# regBlock_slice.net
KiCad netlist of a schematic drawn in EAGLE
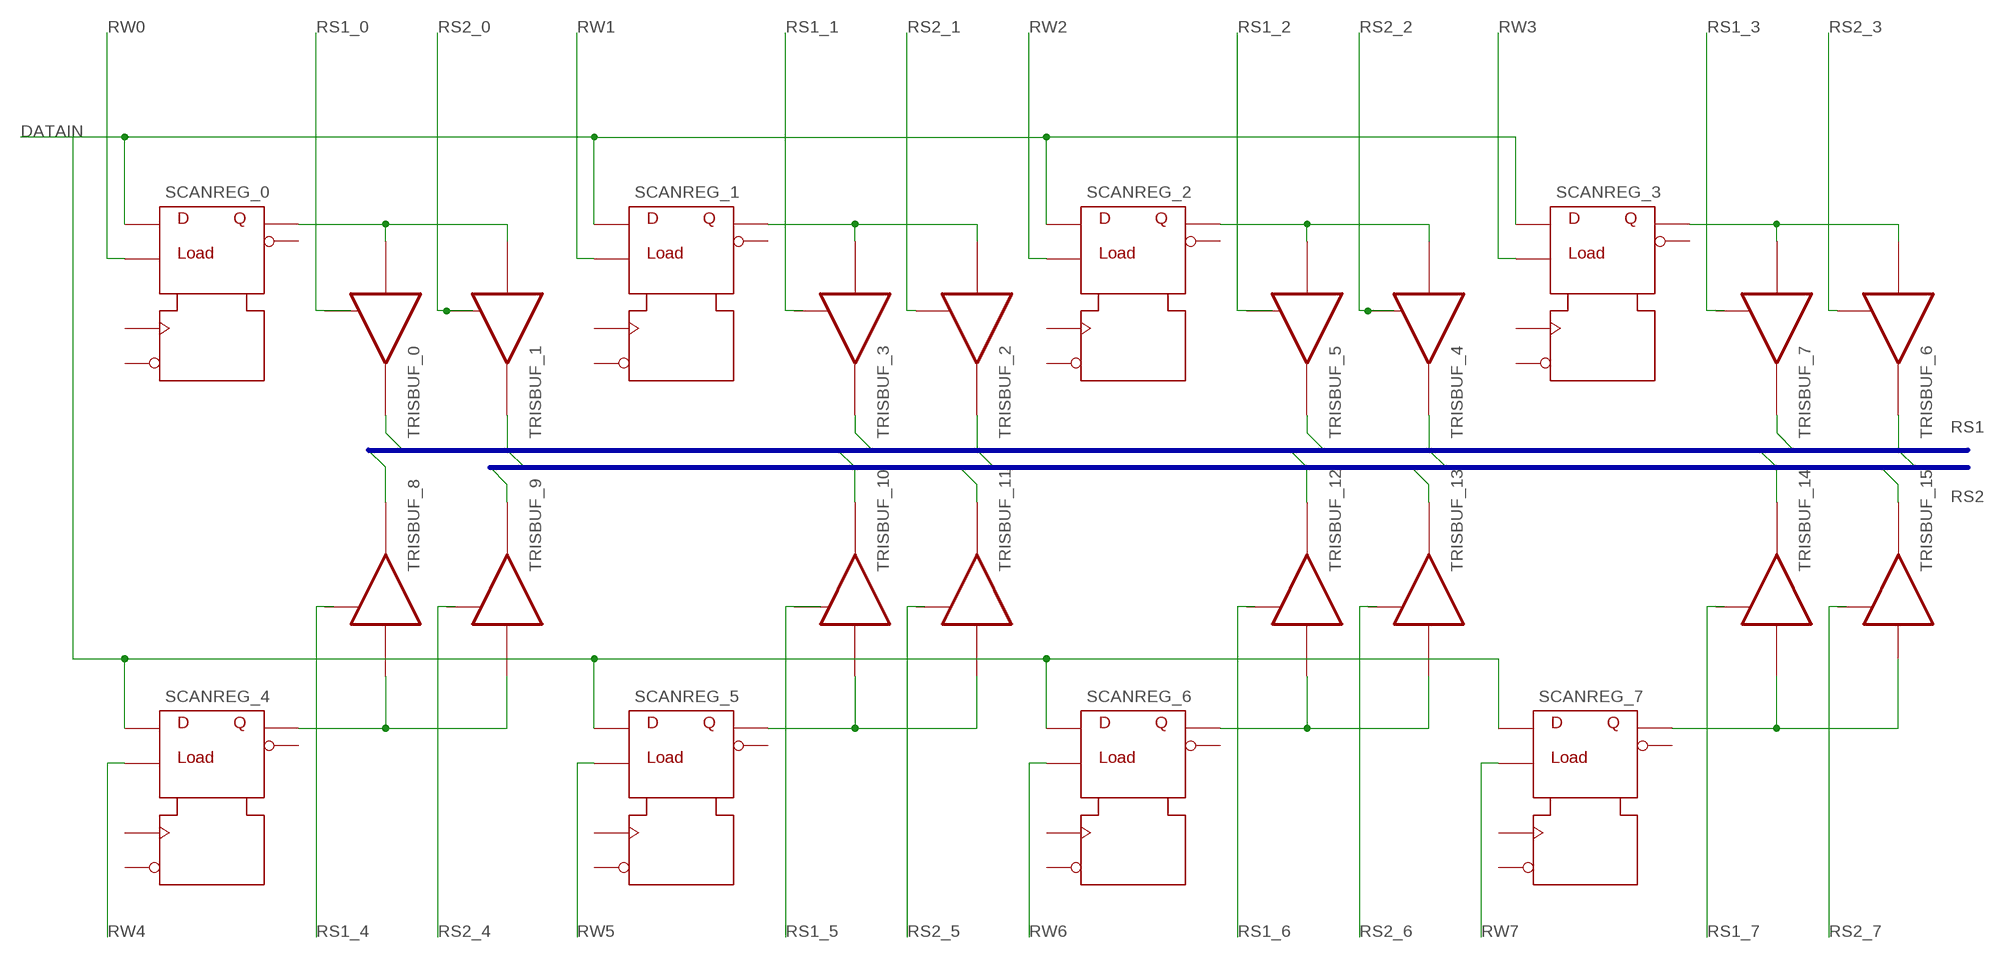
[diagram p0: schematic, sheet 1]

(export (version "E")
  (design (tool "Eeschema 10.0.6"))
  (components
    (comp (ref "SCANREG_0")
      (value "SCANREG")
      (footprint "eagle-import:6PIN")
      (libsource (lib "eagle-import") (part "SCANREG"))
    )
    (comp (ref "SCANREG_1")
      (value "SCANREG")
      (footprint "eagle-import:6PIN")
      (libsource (lib "eagle-import") (part "SCANREG"))
    )
    (comp (ref "SCANREG_2")
      (value "SCANREG")
      (footprint "eagle-import:6PIN")
      (libsource (lib "eagle-import") (part "SCANREG"))
    )
    (comp (ref "SCANREG_3")
      (value "SCANREG")
      (footprint "eagle-import:6PIN")
      (libsource (lib "eagle-import") (part "SCANREG"))
    )
    (comp (ref "SCANREG_4")
      (value "SCANREG")
      (footprint "eagle-import:6PIN")
      (libsource (lib "eagle-import") (part "SCANREG"))
    )
    (comp (ref "SCANREG_5")
      (value "SCANREG")
      (footprint "eagle-import:6PIN")
      (libsource (lib "eagle-import") (part "SCANREG"))
    )
    (comp (ref "SCANREG_6")
      (value "SCANREG")
      (footprint "eagle-import:6PIN")
      (libsource (lib "eagle-import") (part "SCANREG"))
    )
    (comp (ref "SCANREG_7")
      (value "SCANREG")
      (footprint "eagle-import:6PIN")
      (libsource (lib "eagle-import") (part "SCANREG"))
    )
    (comp (ref "TRISBUF_0")
      (value "TRISBUF")
      (footprint "eagle-import:3PIN")
      (libsource (lib "eagle-import") (part "TRISBUF"))
    )
    (comp (ref "TRISBUF_1")
      (value "TRISBUF")
      (footprint "eagle-import:3PIN")
      (libsource (lib "eagle-import") (part "TRISBUF"))
    )
    (comp (ref "TRISBUF_2")
      (value "TRISBUF")
      (footprint "eagle-import:3PIN")
      (libsource (lib "eagle-import") (part "TRISBUF"))
    )
    (comp (ref "TRISBUF_3")
      (value "TRISBUF")
      (footprint "eagle-import:3PIN")
      (libsource (lib "eagle-import") (part "TRISBUF"))
    )
    (comp (ref "TRISBUF_4")
      (value "TRISBUF")
      (footprint "eagle-import:3PIN")
      (libsource (lib "eagle-import") (part "TRISBUF"))
    )
    (comp (ref "TRISBUF_5")
      (value "TRISBUF")
      (footprint "eagle-import:3PIN")
      (libsource (lib "eagle-import") (part "TRISBUF"))
    )
    (comp (ref "TRISBUF_6")
      (value "TRISBUF")
      (footprint "eagle-import:3PIN")
      (libsource (lib "eagle-import") (part "TRISBUF"))
    )
    (comp (ref "TRISBUF_7")
      (value "TRISBUF")
      (footprint "eagle-import:3PIN")
      (libsource (lib "eagle-import") (part "TRISBUF"))
    )
    (comp (ref "TRISBUF_8")
      (value "TRISBUF")
      (footprint "eagle-import:3PIN")
      (libsource (lib "eagle-import") (part "TRISBUF"))
    )
    (comp (ref "TRISBUF_9")
      (value "TRISBUF")
      (footprint "eagle-import:3PIN")
      (libsource (lib "eagle-import") (part "TRISBUF"))
    )
    (comp (ref "TRISBUF_10")
      (value "TRISBUF")
      (footprint "eagle-import:3PIN")
      (libsource (lib "eagle-import") (part "TRISBUF"))
    )
    (comp (ref "TRISBUF_11")
      (value "TRISBUF")
      (footprint "eagle-import:3PIN")
      (libsource (lib "eagle-import") (part "TRISBUF"))
    )
    (comp (ref "TRISBUF_12")
      (value "TRISBUF")
      (footprint "eagle-import:3PIN")
      (libsource (lib "eagle-import") (part "TRISBUF"))
    )
    (comp (ref "TRISBUF_13")
      (value "TRISBUF")
      (footprint "eagle-import:3PIN")
      (libsource (lib "eagle-import") (part "TRISBUF"))
    )
    (comp (ref "TRISBUF_14")
      (value "TRISBUF")
      (footprint "eagle-import:3PIN")
      (libsource (lib "eagle-import") (part "TRISBUF"))
    )
    (comp (ref "TRISBUF_15")
      (value "TRISBUF")
      (footprint "eagle-import:3PIN")
      (libsource (lib "eagle-import") (part "TRISBUF"))
    )
  )
  (nets
    (net (code "3") (name "/B$1") (class "Default")
      (node (ref "TRISBUF_0") (pin "P$2") (pinfunction "O_P$2") (pintype "open_collector"))
      (node (ref "TRISBUF_10") (pin "P$2") (pinfunction "O_P$2") (pintype "open_collector"))
      (node (ref "TRISBUF_12") (pin "P$2") (pinfunction "O_P$2") (pintype "open_collector"))
      (node (ref "TRISBUF_14") (pin "P$2") (pinfunction "O_P$2") (pintype "open_collector"))
      (node (ref "TRISBUF_3") (pin "P$2") (pinfunction "O_P$2") (pintype "open_collector"))
      (node (ref "TRISBUF_5") (pin "P$2") (pinfunction "O_P$2") (pintype "open_collector"))
      (node (ref "TRISBUF_7") (pin "P$2") (pinfunction "O_P$2") (pintype "open_collector"))
      (node (ref "TRISBUF_8") (pin "P$2") (pinfunction "O_P$2") (pintype "open_collector"))
    )
    (net (code "4") (name "/B$2") (class "Default")
      (node (ref "TRISBUF_1") (pin "P$2") (pinfunction "O_P$2") (pintype "open_collector"))
      (node (ref "TRISBUF_11") (pin "P$2") (pinfunction "O_P$2") (pintype "open_collector"))
      (node (ref "TRISBUF_13") (pin "P$2") (pinfunction "O_P$2") (pintype "open_collector"))
      (node (ref "TRISBUF_15") (pin "P$2") (pinfunction "O_P$2") (pintype "open_collector"))
      (node (ref "TRISBUF_2") (pin "P$2") (pinfunction "O_P$2") (pintype "open_collector"))
      (node (ref "TRISBUF_4") (pin "P$2") (pinfunction "O_P$2") (pintype "open_collector"))
      (node (ref "TRISBUF_6") (pin "P$2") (pinfunction "O_P$2") (pintype "open_collector"))
      (node (ref "TRISBUF_9") (pin "P$2") (pinfunction "O_P$2") (pintype "open_collector"))
    )
    (net (code "5") (name "/DATAIN") (class "Default")
      (node (ref "SCANREG_0") (pin "P$2") (pinfunction "D_P$2") (pintype "bidirectional"))
      (node (ref "SCANREG_1") (pin "P$2") (pinfunction "D_P$2") (pintype "bidirectional"))
      (node (ref "SCANREG_2") (pin "P$2") (pinfunction "D_P$2") (pintype "bidirectional"))
      (node (ref "SCANREG_3") (pin "P$2") (pinfunction "D_P$2") (pintype "bidirectional"))
      (node (ref "SCANREG_4") (pin "P$2") (pinfunction "D_P$2") (pintype "bidirectional"))
      (node (ref "SCANREG_5") (pin "P$2") (pinfunction "D_P$2") (pintype "bidirectional"))
      (node (ref "SCANREG_6") (pin "P$2") (pinfunction "D_P$2") (pintype "bidirectional"))
      (node (ref "SCANREG_7") (pin "P$2") (pinfunction "D_P$2") (pintype "bidirectional"))
    )
    (net (code "14") (name "/RS2_0") (class "Default")
      (node (ref "TRISBUF_1") (pin "P$3") (pinfunction "P$1_P$3") (pintype "bidirectional"))
    )
    (net (code "15") (name "/RS2_1") (class "Default")
      (node (ref "TRISBUF_2") (pin "P$3") (pinfunction "P$1_P$3") (pintype "bidirectional"))
    )
    (net (code "16") (name "/RS2_2") (class "Default")
      (node (ref "TRISBUF_4") (pin "P$3") (pinfunction "P$1_P$3") (pintype "bidirectional"))
    )
    (net (code "17") (name "/RS2_3") (class "Default")
      (node (ref "TRISBUF_6") (pin "P$3") (pinfunction "P$1_P$3") (pintype "bidirectional"))
    )
    (net (code "22") (name "/RW0") (class "Default")
      (node (ref "SCANREG_0") (pin "P$3") (pinfunction "LOAD_P$3") (pintype "bidirectional"))
    )
    (net (code "23") (name "/RW1") (class "Default")
      (node (ref "SCANREG_1") (pin "P$3") (pinfunction "LOAD_P$3") (pintype "bidirectional"))
    )
    (net (code "24") (name "/RW2") (class "Default")
      (node (ref "SCANREG_2") (pin "P$3") (pinfunction "LOAD_P$3") (pintype "bidirectional"))
    )
    (net (code "25") (name "/RW3") (class "Default")
      (node (ref "SCANREG_3") (pin "P$3") (pinfunction "LOAD_P$3") (pintype "bidirectional"))
    )
    (net (code "26") (name "/RW4") (class "Default")
      (node (ref "SCANREG_4") (pin "P$3") (pinfunction "LOAD_P$3") (pintype "bidirectional"))
    )
    (net (code "27") (name "/RW5") (class "Default")
      (node (ref "SCANREG_5") (pin "P$3") (pinfunction "LOAD_P$3") (pintype "bidirectional"))
    )
    (net (code "28") (name "/RW6") (class "Default")
      (node (ref "SCANREG_6") (pin "P$3") (pinfunction "LOAD_P$3") (pintype "bidirectional"))
    )
    (net (code "29") (name "/RW7") (class "Default")
      (node (ref "SCANREG_7") (pin "P$3") (pinfunction "LOAD_P$3") (pintype "bidirectional"))
    )
    (net (code "32") (name "Net-(SCANREG_0-Q)") (class "Default")
      (node (ref "SCANREG_0") (pin "P$6") (pinfunction "Q_P$6") (pintype "bidirectional"))
      (node (ref "TRISBUF_0") (pin "P$1") (pinfunction "I_P$1") (pintype "input"))
      (node (ref "TRISBUF_1") (pin "P$1") (pinfunction "I_P$1") (pintype "input"))
    )
    (net (code "33") (name "Net-(SCANREG_1-Q)") (class "Default")
      (node (ref "SCANREG_1") (pin "P$6") (pinfunction "Q_P$6") (pintype "bidirectional"))
      (node (ref "TRISBUF_2") (pin "P$1") (pinfunction "I_P$1") (pintype "input"))
      (node (ref "TRISBUF_3") (pin "P$1") (pinfunction "I_P$1") (pintype "input"))
    )
    (net (code "34") (name "Net-(SCANREG_2-Q)") (class "Default")
      (node (ref "SCANREG_2") (pin "P$6") (pinfunction "Q_P$6") (pintype "bidirectional"))
      (node (ref "TRISBUF_4") (pin "P$1") (pinfunction "I_P$1") (pintype "input"))
      (node (ref "TRISBUF_5") (pin "P$1") (pinfunction "I_P$1") (pintype "input"))
    )
    (net (code "35") (name "Net-(SCANREG_3-Q)") (class "Default")
      (node (ref "SCANREG_3") (pin "P$6") (pinfunction "Q_P$6") (pintype "bidirectional"))
      (node (ref "TRISBUF_6") (pin "P$1") (pinfunction "I_P$1") (pintype "input"))
      (node (ref "TRISBUF_7") (pin "P$1") (pinfunction "I_P$1") (pintype "input"))
    )
    (net (code "36") (name "Net-(SCANREG_4-Q)") (class "Default")
      (node (ref "SCANREG_4") (pin "P$6") (pinfunction "Q_P$6") (pintype "bidirectional"))
      (node (ref "TRISBUF_8") (pin "P$1") (pinfunction "I_P$1") (pintype "input"))
      (node (ref "TRISBUF_9") (pin "P$1") (pinfunction "I_P$1") (pintype "input"))
    )
    (net (code "37") (name "Net-(SCANREG_5-Q)") (class "Default")
      (node (ref "SCANREG_5") (pin "P$6") (pinfunction "Q_P$6") (pintype "bidirectional"))
      (node (ref "TRISBUF_10") (pin "P$1") (pinfunction "I_P$1") (pintype "input"))
      (node (ref "TRISBUF_11") (pin "P$1") (pinfunction "I_P$1") (pintype "input"))
    )
    (net (code "38") (name "Net-(SCANREG_6-Q)") (class "Default")
      (node (ref "SCANREG_6") (pin "P$6") (pinfunction "Q_P$6") (pintype "bidirectional"))
      (node (ref "TRISBUF_12") (pin "P$1") (pinfunction "I_P$1") (pintype "input"))
      (node (ref "TRISBUF_13") (pin "P$1") (pinfunction "I_P$1") (pintype "input"))
    )
    (net (code "39") (name "Net-(SCANREG_7-Q)") (class "Default")
      (node (ref "SCANREG_7") (pin "P$6") (pinfunction "Q_P$6") (pintype "bidirectional"))
      (node (ref "TRISBUF_14") (pin "P$1") (pinfunction "I_P$1") (pintype "input"))
    )
    (net (code "40") (name "unconnected-(SCANREG_0-CLOCK-PadP$1)") (class "Default")
      (node (ref "SCANREG_0") (pin "P$1") (pinfunction "CLOCK_P$1") (pintype "bidirectional"))
    )
    (net (code "41") (name "unconnected-(SCANREG_0-NQ-PadP$4)") (class "Default")
      (node (ref "SCANREG_0") (pin "P$4") (pinfunction "NQ_P$4") (pintype "bidirectional"))
    )
    (net (code "42") (name "unconnected-(SCANREG_0-NRESET-PadP$5)") (class "Default")
      (node (ref "SCANREG_0") (pin "P$5") (pinfunction "NRESET_P$5") (pintype "bidirectional"))
    )
    (net (code "43") (name "unconnected-(SCANREG_1-CLOCK-PadP$1)") (class "Default")
      (node (ref "SCANREG_1") (pin "P$1") (pinfunction "CLOCK_P$1") (pintype "bidirectional"))
    )
    (net (code "44") (name "unconnected-(SCANREG_1-NQ-PadP$4)") (class "Default")
      (node (ref "SCANREG_1") (pin "P$4") (pinfunction "NQ_P$4") (pintype "bidirectional"))
    )
    (net (code "45") (name "unconnected-(SCANREG_1-NRESET-PadP$5)") (class "Default")
      (node (ref "SCANREG_1") (pin "P$5") (pinfunction "NRESET_P$5") (pintype "bidirectional"))
    )
    (net (code "46") (name "unconnected-(SCANREG_2-CLOCK-PadP$1)") (class "Default")
      (node (ref "SCANREG_2") (pin "P$1") (pinfunction "CLOCK_P$1") (pintype "bidirectional"))
    )
    (net (code "47") (name "unconnected-(SCANREG_2-NQ-PadP$4)") (class "Default")
      (node (ref "SCANREG_2") (pin "P$4") (pinfunction "NQ_P$4") (pintype "bidirectional"))
    )
    (net (code "48") (name "unconnected-(SCANREG_2-NRESET-PadP$5)") (class "Default")
      (node (ref "SCANREG_2") (pin "P$5") (pinfunction "NRESET_P$5") (pintype "bidirectional"))
    )
    (net (code "49") (name "unconnected-(SCANREG_3-CLOCK-PadP$1)") (class "Default")
      (node (ref "SCANREG_3") (pin "P$1") (pinfunction "CLOCK_P$1") (pintype "bidirectional"))
    )
    (net (code "50") (name "unconnected-(SCANREG_3-NQ-PadP$4)") (class "Default")
      (node (ref "SCANREG_3") (pin "P$4") (pinfunction "NQ_P$4") (pintype "bidirectional"))
    )
    (net (code "51") (name "unconnected-(SCANREG_3-NRESET-PadP$5)") (class "Default")
      (node (ref "SCANREG_3") (pin "P$5") (pinfunction "NRESET_P$5") (pintype "bidirectional"))
    )
    (net (code "52") (name "unconnected-(SCANREG_4-CLOCK-PadP$1)") (class "Default")
      (node (ref "SCANREG_4") (pin "P$1") (pinfunction "CLOCK_P$1") (pintype "bidirectional"))
    )
    (net (code "53") (name "unconnected-(SCANREG_4-NQ-PadP$4)") (class "Default")
      (node (ref "SCANREG_4") (pin "P$4") (pinfunction "NQ_P$4") (pintype "bidirectional"))
    )
    (net (code "54") (name "unconnected-(SCANREG_4-NRESET-PadP$5)") (class "Default")
      (node (ref "SCANREG_4") (pin "P$5") (pinfunction "NRESET_P$5") (pintype "bidirectional"))
    )
    (net (code "55") (name "unconnected-(SCANREG_5-CLOCK-PadP$1)") (class "Default")
      (node (ref "SCANREG_5") (pin "P$1") (pinfunction "CLOCK_P$1") (pintype "bidirectional"))
    )
    (net (code "56") (name "unconnected-(SCANREG_5-NQ-PadP$4)") (class "Default")
      (node (ref "SCANREG_5") (pin "P$4") (pinfunction "NQ_P$4") (pintype "bidirectional"))
    )
    (net (code "57") (name "unconnected-(SCANREG_5-NRESET-PadP$5)") (class "Default")
      (node (ref "SCANREG_5") (pin "P$5") (pinfunction "NRESET_P$5") (pintype "bidirectional"))
    )
    (net (code "58") (name "unconnected-(SCANREG_6-CLOCK-PadP$1)") (class "Default")
      (node (ref "SCANREG_6") (pin "P$1") (pinfunction "CLOCK_P$1") (pintype "bidirectional"))
    )
    (net (code "59") (name "unconnected-(SCANREG_6-NQ-PadP$4)") (class "Default")
      (node (ref "SCANREG_6") (pin "P$4") (pinfunction "NQ_P$4") (pintype "bidirectional"))
    )
    (net (code "60") (name "unconnected-(SCANREG_6-NRESET-PadP$5)") (class "Default")
      (node (ref "SCANREG_6") (pin "P$5") (pinfunction "NRESET_P$5") (pintype "bidirectional"))
    )
    (net (code "61") (name "unconnected-(SCANREG_7-CLOCK-PadP$1)") (class "Default")
      (node (ref "SCANREG_7") (pin "P$1") (pinfunction "CLOCK_P$1") (pintype "bidirectional"))
    )
    (net (code "62") (name "unconnected-(SCANREG_7-NQ-PadP$4)") (class "Default")
      (node (ref "SCANREG_7") (pin "P$4") (pinfunction "NQ_P$4") (pintype "bidirectional"))
    )
    (net (code "63") (name "unconnected-(SCANREG_7-NRESET-PadP$5)") (class "Default")
      (node (ref "SCANREG_7") (pin "P$5") (pinfunction "NRESET_P$5") (pintype "bidirectional"))
    )
    (net (code "64") (name "unconnected-(TRISBUF_0-P$1-PadP$3)") (class "Default")
      (node (ref "TRISBUF_0") (pin "P$3") (pinfunction "P$1_P$3") (pintype "bidirectional"))
    )
    (net (code "65") (name "unconnected-(TRISBUF_3-P$1-PadP$3)") (class "Default")
      (node (ref "TRISBUF_3") (pin "P$3") (pinfunction "P$1_P$3") (pintype "bidirectional"))
    )
    (net (code "66") (name "unconnected-(TRISBUF_5-P$1-PadP$3)") (class "Default")
      (node (ref "TRISBUF_5") (pin "P$3") (pinfunction "P$1_P$3") (pintype "bidirectional"))
    )
    (net (code "67") (name "unconnected-(TRISBUF_7-P$1-PadP$3)") (class "Default")
      (node (ref "TRISBUF_7") (pin "P$3") (pinfunction "P$1_P$3") (pintype "bidirectional"))
    )
    (net (code "68") (name "unconnected-(TRISBUF_8-P$1-PadP$3)") (class "Default")
      (node (ref "TRISBUF_8") (pin "P$3") (pinfunction "P$1_P$3") (pintype "bidirectional"))
    )
    (net (code "69") (name "unconnected-(TRISBUF_9-P$1-PadP$3)") (class "Default")
      (node (ref "TRISBUF_9") (pin "P$3") (pinfunction "P$1_P$3") (pintype "bidirectional"))
    )
    (net (code "70") (name "unconnected-(TRISBUF_10-P$1-PadP$3)") (class "Default")
      (node (ref "TRISBUF_10") (pin "P$3") (pinfunction "P$1_P$3") (pintype "bidirectional"))
    )
    (net (code "71") (name "unconnected-(TRISBUF_11-P$1-PadP$3)") (class "Default")
      (node (ref "TRISBUF_11") (pin "P$3") (pinfunction "P$1_P$3") (pintype "bidirectional"))
    )
    (net (code "72") (name "unconnected-(TRISBUF_12-P$1-PadP$3)") (class "Default")
      (node (ref "TRISBUF_12") (pin "P$3") (pinfunction "P$1_P$3") (pintype "bidirectional"))
    )
    (net (code "73") (name "unconnected-(TRISBUF_13-P$1-PadP$3)") (class "Default")
      (node (ref "TRISBUF_13") (pin "P$3") (pinfunction "P$1_P$3") (pintype "bidirectional"))
    )
    (net (code "74") (name "unconnected-(TRISBUF_14-P$1-PadP$3)") (class "Default")
      (node (ref "TRISBUF_14") (pin "P$3") (pinfunction "P$1_P$3") (pintype "bidirectional"))
    )
    (net (code "75") (name "unconnected-(TRISBUF_15-I-PadP$1)") (class "Default")
      (node (ref "TRISBUF_15") (pin "P$1") (pinfunction "I_P$1") (pintype "input"))
    )
    (net (code "76") (name "unconnected-(TRISBUF_15-P$1-PadP$3)") (class "Default")
      (node (ref "TRISBUF_15") (pin "P$3") (pinfunction "P$1_P$3") (pintype "bidirectional"))
    )
  )
)
